# DigiDash.net
KiCad netlist of a schematic drawn in EAGLE
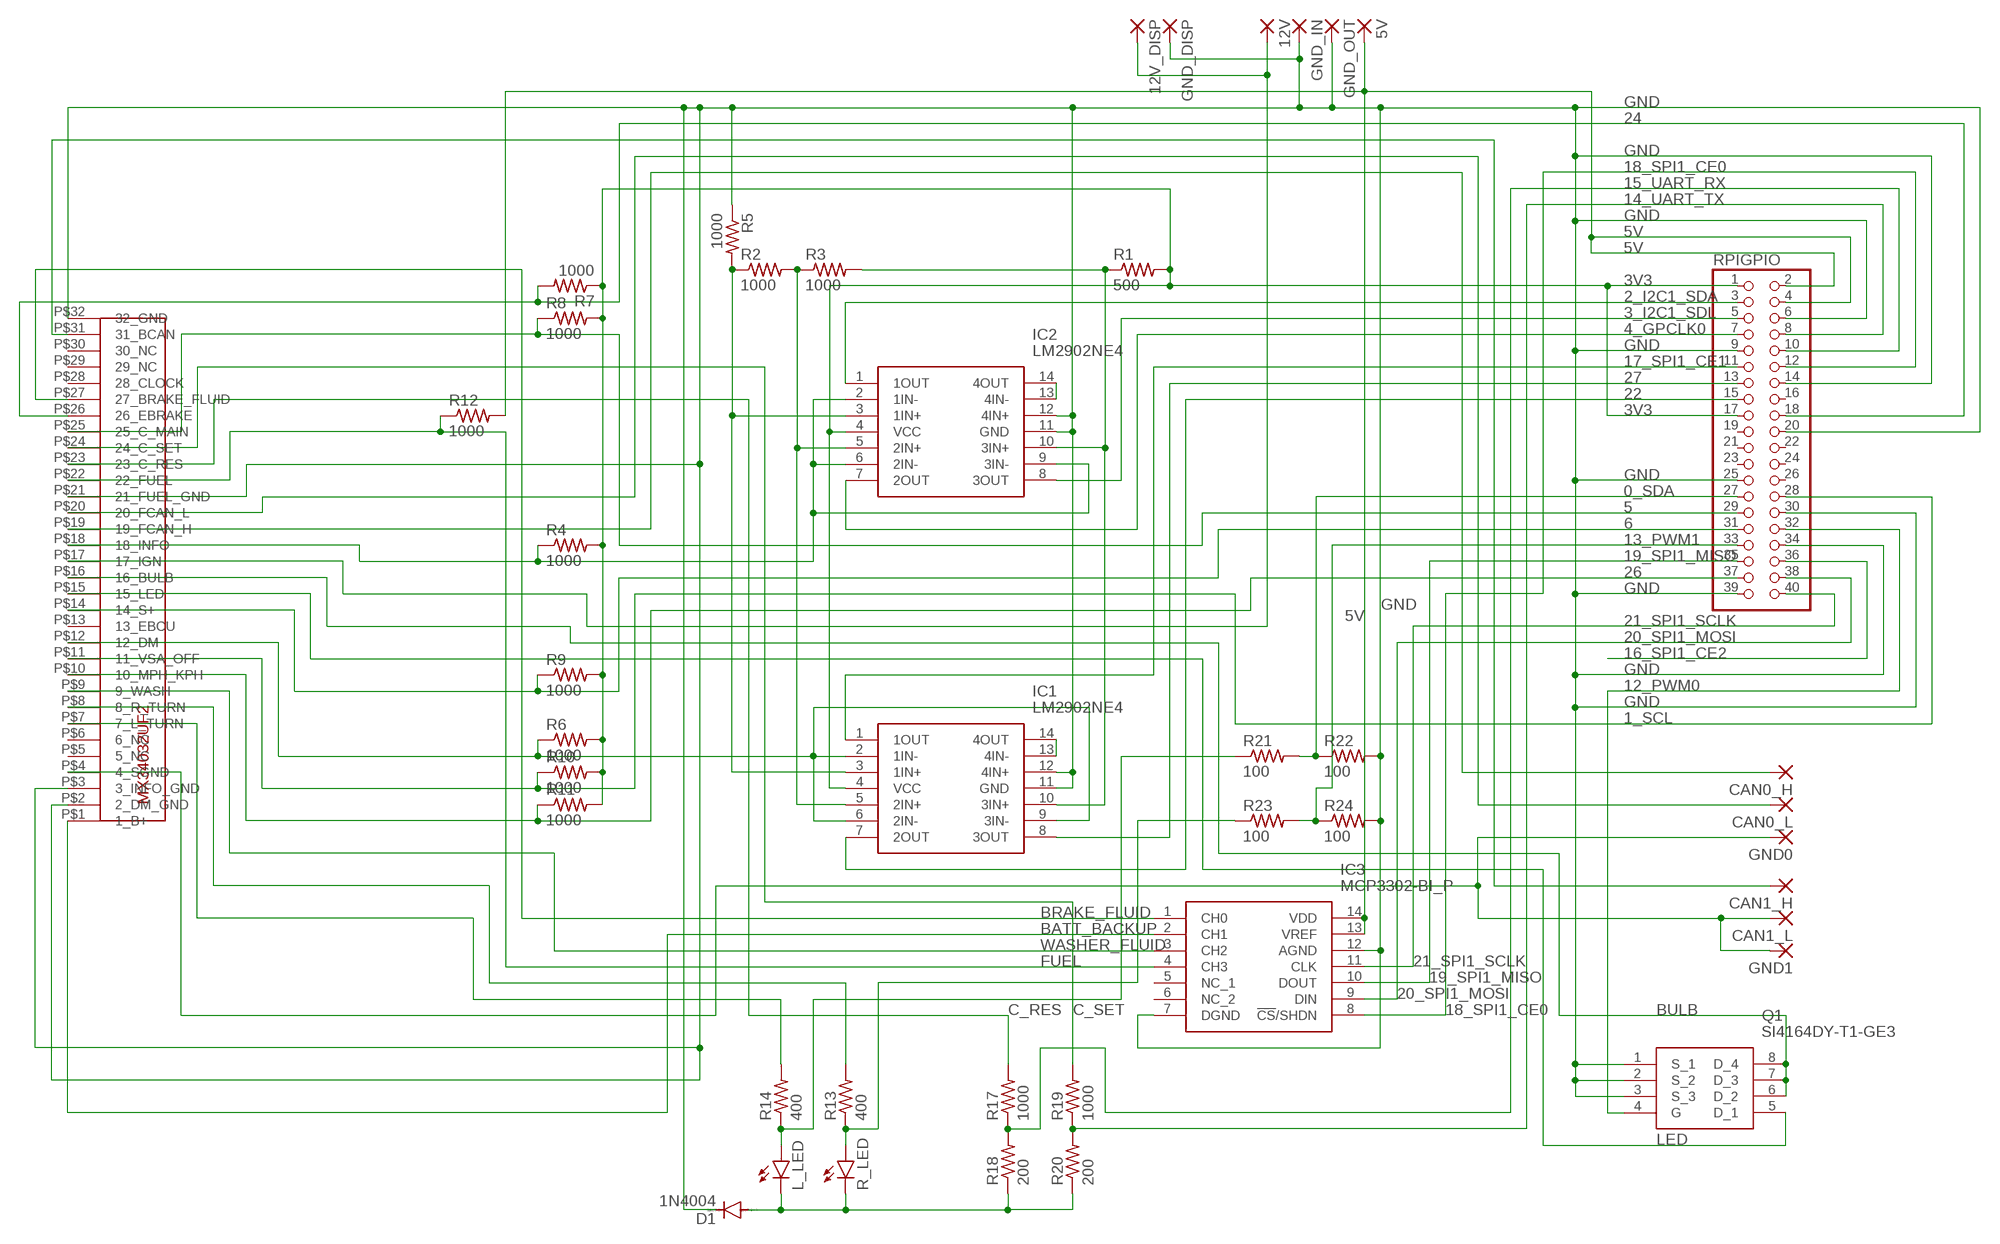
[diagram p0: schematic, sheet 1]

(export (version "E")
  (design (tool "Eeschema 10.0.6"))
  (components
    (comp (ref "5V")
      (value "3,81/1,4")
      (footprint "eagle-import:3,81_1,4")
      (libsource (lib "eagle-import") (part "3,81/1,4"))
    )
    (comp (ref "12V")
      (value "3,81/1,4")
      (footprint "eagle-import:3,81_1,4")
      (libsource (lib "eagle-import") (part "3,81/1,4"))
    )
    (comp (ref "12V_DISP")
      (value "3,81/1,4")
      (footprint "eagle-import:3,81_1,4")
      (libsource (lib "eagle-import") (part "3,81/1,4"))
    )
    (comp (ref "CAN0_H")
      (value "3,81/1,4")
      (footprint "eagle-import:3,81_1,4")
      (libsource (lib "eagle-import") (part "3,81/1,4"))
    )
    (comp (ref "CAN0_L")
      (value "3,81/1,4")
      (footprint "eagle-import:3,81_1,4")
      (libsource (lib "eagle-import") (part "3,81/1,4"))
    )
    (comp (ref "CAN1_H")
      (value "3,81/1,4")
      (footprint "eagle-import:3,81_1,4")
      (libsource (lib "eagle-import") (part "3,81/1,4"))
    )
    (comp (ref "CAN1_L")
      (value "3,81/1,4")
      (footprint "eagle-import:3,81_1,4")
      (libsource (lib "eagle-import") (part "3,81/1,4"))
    )
    (comp (ref "D1")
      (value "1N4004")
      (footprint "eagle-import:DO41-10")
      (libsource (lib "eagle-import") (part "1N4004"))
    )
    (comp (ref "GND0")
      (value "3,81/1,4")
      (footprint "eagle-import:3,81_1,4")
      (libsource (lib "eagle-import") (part "3,81/1,4"))
    )
    (comp (ref "GND1")
      (value "3,81/1,4")
      (footprint "eagle-import:3,81_1,4")
      (libsource (lib "eagle-import") (part "3,81/1,4"))
    )
    (comp (ref "GND_DISP")
      (value "3,81/1,4")
      (footprint "eagle-import:3,81_1,4")
      (libsource (lib "eagle-import") (part "3,81/1,4"))
    )
    (comp (ref "GND_IN")
      (value "3,81/1,4")
      (footprint "eagle-import:3,81_1,4")
      (libsource (lib "eagle-import") (part "3,81/1,4"))
    )
    (comp (ref "GND_OUT")
      (value "3,81/1,4")
      (footprint "eagle-import:3,81_1,4")
      (libsource (lib "eagle-import") (part "3,81/1,4"))
    )
    (comp (ref "IC1")
      (value "LM2902NE4")
      (footprint "eagle-import:DIP794W53P254L1930H508Q14N")
      (fields (field (name "MOUSER_PART_NUMBER") "595-LM2902NE4"))
      (libsource (lib "eagle-import") (part "LM2902NE4"))
    )
    (comp (ref "IC2")
      (value "LM2902NE4")
      (footprint "eagle-import:DIP794W53P254L1930H508Q14N")
      (fields (field (name "MOUSER_PART_NUMBER") "595-LM2902NE4"))
      (libsource (lib "eagle-import") (part "LM2902NE4"))
    )
    (comp (ref "IC3")
      (value "MCP3302-BI_P")
      (footprint "eagle-import:DIP781W56P254L1918H533Q14N")
      (fields
        (field (name "ARROW_PART_NUMBER") "MCP3302-BI/P")
        (field (name "MOUSER_PART_NUMBER") "579-MCP3302-BI/P")
      )
      (libsource (lib "eagle-import") (part "MCP3302-BI_P"))
    )
    (comp (ref "L_LED")
      (value "LED3MM")
      (footprint "eagle-import:LED3MM")
      (libsource (lib "eagle-import") (part "LED3MM"))
    )
    (comp (ref "Q1")
      (value "SI4164DY-T1-GE3")
      (footprint "eagle-import:SOIC127P600X175-8N")
      (fields (field (name "MOUSER_PART_NUMBER") "781-SI4164DY-T1-GE3"))
      (libsource (lib "eagle-import") (part "SI4164DY-T1-GE3"))
    )
    (comp (ref "R1")
      (value "500")
      (footprint "eagle-import:0204_7")
      (libsource (lib "eagle-import") (part "R-US_0204/7"))
    )
    (comp (ref "R2")
      (value "1000")
      (footprint "eagle-import:0204_7")
      (libsource (lib "eagle-import") (part "R-US_0204/7"))
    )
    (comp (ref "R3")
      (value "1000")
      (footprint "eagle-import:0204_7")
      (libsource (lib "eagle-import") (part "R-US_0204/7"))
    )
    (comp (ref "R4")
      (value "1000")
      (footprint "eagle-import:0204_7")
      (libsource (lib "eagle-import") (part "R-US_0204/7"))
    )
    (comp (ref "R5")
      (value "1000")
      (footprint "eagle-import:0204_7")
      (libsource (lib "eagle-import") (part "R-US_0204/7"))
    )
    (comp (ref "R6")
      (value "1000")
      (footprint "eagle-import:0204_7")
      (libsource (lib "eagle-import") (part "R-US_0204/7"))
    )
    (comp (ref "R7")
      (value "1000")
      (footprint "eagle-import:0204_7")
      (libsource (lib "eagle-import") (part "R-US_0204/7"))
    )
    (comp (ref "R8")
      (value "1000")
      (footprint "eagle-import:0204_7")
      (libsource (lib "eagle-import") (part "R-US_0204/7"))
    )
    (comp (ref "R9")
      (value "1000")
      (footprint "eagle-import:0204_7")
      (libsource (lib "eagle-import") (part "R-US_0204/7"))
    )
    (comp (ref "R10")
      (value "1000")
      (footprint "eagle-import:0204_7")
      (libsource (lib "eagle-import") (part "R-US_0204/7"))
    )
    (comp (ref "R11")
      (value "1000")
      (footprint "eagle-import:0204_7")
      (libsource (lib "eagle-import") (part "R-US_0204/7"))
    )
    (comp (ref "R12")
      (value "1000")
      (footprint "eagle-import:0204_7")
      (libsource (lib "eagle-import") (part "R-US_0204/7"))
    )
    (comp (ref "R13")
      (value "400")
      (footprint "eagle-import:0204_7")
      (libsource (lib "eagle-import") (part "R-US_0204/7"))
    )
    (comp (ref "R14")
      (value "400")
      (footprint "eagle-import:0204_7")
      (libsource (lib "eagle-import") (part "R-US_0204/7"))
    )
    (comp (ref "R17")
      (value "1000")
      (footprint "eagle-import:0204_7")
      (libsource (lib "eagle-import") (part "R-US_0204/7"))
    )
    (comp (ref "R18")
      (value "200")
      (footprint "eagle-import:0204_7")
      (libsource (lib "eagle-import") (part "R-US_0204/7"))
    )
    (comp (ref "R19")
      (value "1000")
      (footprint "eagle-import:0204_7")
      (libsource (lib "eagle-import") (part "R-US_0204/7"))
    )
    (comp (ref "R20")
      (value "200")
      (footprint "eagle-import:0204_7")
      (libsource (lib "eagle-import") (part "R-US_0204/7"))
    )
    (comp (ref "R21")
      (value "100")
      (footprint "eagle-import:0204_7")
      (libsource (lib "eagle-import") (part "R-US_0204/7"))
    )
    (comp (ref "R22")
      (value "100")
      (footprint "eagle-import:0204_7")
      (libsource (lib "eagle-import") (part "R-US_0204/7"))
    )
    (comp (ref "R23")
      (value "100")
      (footprint "eagle-import:0204_7")
      (libsource (lib "eagle-import") (part "R-US_0204/7"))
    )
    (comp (ref "R24")
      (value "100")
      (footprint "eagle-import:0204_7")
      (libsource (lib "eagle-import") (part "R-US_0204/7"))
    )
    (comp (ref "RPIGPIO")
      (value "PINHD-2X20")
      (footprint "eagle-import:2X20")
      (libsource (lib "eagle-import") (part "PINHD-2X20"))
    )
    (comp (ref "R_LED")
      (value "LED3MM")
      (footprint "eagle-import:LED3MM")
      (libsource (lib "eagle-import") (part "LED3MM"))
    )
    (comp (ref "U$1")
      (value "MX34032UF2")
      (footprint "eagle-import:MX34032UF2")
      (libsource (lib "eagle-import") (part "MX34032UF2"))
    )
  )
  (nets
    (net (code "1") (name "/0_SDA") (class "Default")
      (node (ref "R21") (pin "2") (pinfunction "2_2") (pintype "passive"))
      (node (ref "R22") (pin "1") (pinfunction "1_1") (pintype "passive"))
      (node (ref "RPIGPIO") (pin "27") (pinfunction "27_27") (pintype "passive"))
    )
    (net (code "2") (name "/1_SCL") (class "Default")
      (node (ref "R10") (pin "1") (pinfunction "1_1") (pintype "passive"))
      (node (ref "RPIGPIO") (pin "28") (pinfunction "28_28") (pintype "passive"))
      (node (ref "U$1") (pin "P$11") (pinfunction "11_VSA_OFF_P$11") (pintype "bidirectional"))
    )
    (net (code "3") (name "/2_I2C1_SDA") (class "Default")
      (node (ref "IC2") (pin "1") (pinfunction "1OUT_1") (pintype "bidirectional"))
      (node (ref "RPIGPIO") (pin "3") (pinfunction "3_3") (pintype "passive"))
    )
    (net (code "4") (name "/3V3") (class "Default")
      (node (ref "IC1") (pin "4") (pinfunction "VCC_4") (pintype "bidirectional"))
      (node (ref "IC2") (pin "4") (pinfunction "VCC_4") (pintype "bidirectional"))
      (node (ref "R1") (pin "2") (pinfunction "2_2") (pintype "passive"))
      (node (ref "R10") (pin "2") (pinfunction "2_2") (pintype "passive"))
      (node (ref "R11") (pin "2") (pinfunction "2_2") (pintype "passive"))
      (node (ref "R4") (pin "2") (pinfunction "2_2") (pintype "passive"))
      (node (ref "R6") (pin "2") (pinfunction "2_2") (pintype "passive"))
      (node (ref "R7") (pin "1") (pinfunction "1_1") (pintype "passive"))
      (node (ref "R8") (pin "2") (pinfunction "2_2") (pintype "passive"))
      (node (ref "R9") (pin "2") (pinfunction "2_2") (pintype "passive"))
      (node (ref "RPIGPIO") (pin "1") (pinfunction "1_1") (pintype "passive"))
      (node (ref "RPIGPIO") (pin "17") (pinfunction "17_17") (pintype "passive"))
    )
    (net (code "5") (name "/3_I2C1_SDL") (class "Default")
      (node (ref "IC2") (pin "8") (pinfunction "3OUT_8") (pintype "bidirectional"))
      (node (ref "RPIGPIO") (pin "5") (pinfunction "5_5") (pintype "passive"))
    )
    (net (code "6") (name "/4_GPCLK0") (class "Default")
      (node (ref "IC2") (pin "7") (pinfunction "2OUT_7") (pintype "bidirectional"))
      (node (ref "RPIGPIO") (pin "7") (pinfunction "7_7") (pintype "passive"))
    )
    (net (code "7") (name "/5") (class "Default")
      (node (ref "R8") (pin "1") (pinfunction "1_1") (pintype "passive"))
      (node (ref "RPIGPIO") (pin "29") (pinfunction "29_29") (pintype "passive"))
      (node (ref "U$1") (pin "P$25") (pinfunction "25_C_MAIN_P$25") (pintype "bidirectional"))
    )
    (net (code "8") (name "/5V") (class "Default")
      (node (ref "5V") (pin "1") (pinfunction "P_1") (pintype "passive"))
      (node (ref "IC3") (pin "13") (pinfunction "VREF_13") (pintype "bidirectional"))
      (node (ref "IC3") (pin "14") (pinfunction "VDD_14") (pintype "bidirectional"))
      (node (ref "R12") (pin "2") (pinfunction "2_2") (pintype "passive"))
      (node (ref "RPIGPIO") (pin "2") (pinfunction "2_2") (pintype "passive"))
      (node (ref "RPIGPIO") (pin "4") (pinfunction "4_4") (pintype "passive"))
    )
    (net (code "9") (name "/6") (class "Default")
      (node (ref "R9") (pin "1") (pinfunction "1_1") (pintype "passive"))
      (node (ref "RPIGPIO") (pin "31") (pinfunction "31_31") (pintype "passive"))
      (node (ref "U$1") (pin "P$14") (pinfunction "14_S+_P$14") (pintype "bidirectional"))
    )
    (net (code "10") (name "/12_PWM0") (class "Default")
      (node (ref "Q1") (pin "4") (pinfunction "G_4") (pintype "bidirectional"))
      (node (ref "RPIGPIO") (pin "32") (pinfunction "32_32") (pintype "passive"))
    )
    (net (code "11") (name "/13_PWM1") (class "Default")
      (node (ref "R23") (pin "2") (pinfunction "2_2") (pintype "passive"))
      (node (ref "R24") (pin "1") (pinfunction "1_1") (pintype "passive"))
      (node (ref "RPIGPIO") (pin "33") (pinfunction "33_33") (pintype "passive"))
    )
    (net (code "12") (name "/14_UART_TX") (class "Default")
      (node (ref "R19") (pin "1") (pinfunction "1_1") (pintype "passive"))
      (node (ref "R20") (pin "2") (pinfunction "2_2") (pintype "passive"))
      (node (ref "RPIGPIO") (pin "8") (pinfunction "8_8") (pintype "passive"))
    )
    (net (code "13") (name "/15_UART_RX") (class "Default")
      (node (ref "R17") (pin "1") (pinfunction "1_1") (pintype "passive"))
      (node (ref "R18") (pin "2") (pinfunction "2_2") (pintype "passive"))
      (node (ref "RPIGPIO") (pin "10") (pinfunction "10_10") (pintype "passive"))
    )
    (net (code "14") (name "/16_SPI1_CE2") (class "Default")
      (node (ref "RPIGPIO") (pin "36") (pinfunction "36_36") (pintype "passive"))
    )
    (net (code "15") (name "/17_SPI1_CE1") (class "Default")
      (node (ref "IC1") (pin "1") (pinfunction "1OUT_1") (pintype "bidirectional"))
      (node (ref "RPIGPIO") (pin "11") (pinfunction "11_11") (pintype "passive"))
    )
    (net (code "16") (name "/18_SPI1_CE0") (class "Default")
      (node (ref "IC3") (pin "8") (pinfunction "~{CS}/SHDN_8") (pintype "bidirectional"))
      (node (ref "RPIGPIO") (pin "12") (pinfunction "12_12") (pintype "passive"))
    )
    (net (code "17") (name "/19_SPI1_MISO") (class "Default")
      (node (ref "IC3") (pin "10") (pinfunction "DOUT_10") (pintype "bidirectional"))
      (node (ref "RPIGPIO") (pin "35") (pinfunction "35_35") (pintype "passive"))
    )
    (net (code "18") (name "/20_SPI1_MOSI") (class "Default")
      (node (ref "IC3") (pin "9") (pinfunction "DIN_9") (pintype "bidirectional"))
      (node (ref "RPIGPIO") (pin "38") (pinfunction "38_38") (pintype "passive"))
    )
    (net (code "19") (name "/21_SPI1_SCLK") (class "Default")
      (node (ref "IC3") (pin "11") (pinfunction "CLK_11") (pintype "bidirectional"))
      (node (ref "RPIGPIO") (pin "40") (pinfunction "40_40") (pintype "passive"))
    )
    (net (code "20") (name "/22") (class "Default")
      (node (ref "IC1") (pin "7") (pinfunction "2OUT_7") (pintype "bidirectional"))
      (node (ref "RPIGPIO") (pin "15") (pinfunction "15_15") (pintype "passive"))
    )
    (net (code "21") (name "/24") (class "Default")
      (node (ref "R7") (pin "2") (pinfunction "2_2") (pintype "passive"))
      (node (ref "RPIGPIO") (pin "18") (pinfunction "18_18") (pintype "passive"))
      (node (ref "U$1") (pin "P$26") (pinfunction "26_EBRAKE_P$26") (pintype "bidirectional"))
    )
    (net (code "22") (name "/26") (class "Default")
      (node (ref "R11") (pin "1") (pinfunction "1_1") (pintype "passive"))
      (node (ref "RPIGPIO") (pin "37") (pinfunction "37_37") (pintype "passive"))
      (node (ref "U$1") (pin "P$10") (pinfunction "10_MPH_KPH_P$10") (pintype "bidirectional"))
    )
    (net (code "23") (name "/27") (class "Default")
      (node (ref "IC1") (pin "8") (pinfunction "3OUT_8") (pintype "bidirectional"))
      (node (ref "RPIGPIO") (pin "13") (pinfunction "13_13") (pintype "passive"))
    )
    (net (code "24") (name "/BATT_BACKUP") (class "Default")
      (node (ref "IC3") (pin "2") (pinfunction "CH1_2") (pintype "bidirectional"))
      (node (ref "U$1") (pin "P$1") (pinfunction "1_B+_P$1") (pintype "bidirectional"))
    )
    (net (code "25") (name "/BRAKE_FLUID") (class "Default")
      (node (ref "IC3") (pin "1") (pinfunction "CH0_1") (pintype "bidirectional"))
      (node (ref "U$1") (pin "P$27") (pinfunction "27_BRAKE_FLUID_P$27") (pintype "bidirectional"))
    )
    (net (code "26") (name "/BULB") (class "Default")
      (node (ref "Q1") (pin "6") (pinfunction "D_2_6") (pintype "bidirectional"))
      (node (ref "Q1") (pin "7") (pinfunction "D_3_7") (pintype "bidirectional"))
      (node (ref "Q1") (pin "8") (pinfunction "D_4_8") (pintype "bidirectional"))
      (node (ref "U$1") (pin "P$16") (pinfunction "16_BULB_P$16") (pintype "bidirectional"))
    )
    (net (code "27") (name "/C_RES") (class "Default")
      (node (ref "R17") (pin "2") (pinfunction "2_2") (pintype "passive"))
      (node (ref "U$1") (pin "P$23") (pinfunction "23_C_RES_P$23") (pintype "bidirectional"))
    )
    (net (code "28") (name "/C_SET") (class "Default")
      (node (ref "R19") (pin "2") (pinfunction "2_2") (pintype "passive"))
      (node (ref "U$1") (pin "P$24") (pinfunction "24_C_SET_P$24") (pintype "bidirectional"))
    )
    (net (code "29") (name "/FUEL") (class "Default")
      (node (ref "IC3") (pin "4") (pinfunction "CH3_4") (pintype "bidirectional"))
      (node (ref "R12") (pin "1") (pinfunction "1_1") (pintype "passive"))
      (node (ref "U$1") (pin "P$22") (pinfunction "22_FUEL_P$22") (pintype "bidirectional"))
    )
    (net (code "30") (name "/GND") (class "Default")
      (node (ref "D1") (pin "C") (pinfunction "C_C") (pintype "passive"))
      (node (ref "GND_DISP") (pin "1") (pinfunction "P_1") (pintype "passive"))
      (node (ref "GND_IN") (pin "1") (pinfunction "P_1") (pintype "passive"))
      (node (ref "GND_OUT") (pin "1") (pinfunction "P_1") (pintype "passive"))
      (node (ref "IC1") (pin "11") (pinfunction "GND_11") (pintype "bidirectional"))
      (node (ref "IC1") (pin "12") (pinfunction "4IN+_12") (pintype "bidirectional"))
      (node (ref "IC2") (pin "11") (pinfunction "GND_11") (pintype "bidirectional"))
      (node (ref "IC2") (pin "12") (pinfunction "4IN+_12") (pintype "bidirectional"))
      (node (ref "IC3") (pin "12") (pinfunction "AGND_12") (pintype "bidirectional"))
      (node (ref "IC3") (pin "7") (pinfunction "DGND_7") (pintype "bidirectional"))
      (node (ref "Q1") (pin "1") (pinfunction "S_1_1") (pintype "bidirectional"))
      (node (ref "Q1") (pin "2") (pinfunction "S_2_2") (pintype "bidirectional"))
      (node (ref "Q1") (pin "3") (pinfunction "S_3_3") (pintype "bidirectional"))
      (node (ref "R22") (pin "2") (pinfunction "2_2") (pintype "passive"))
      (node (ref "R24") (pin "2") (pinfunction "2_2") (pintype "passive"))
      (node (ref "R5") (pin "1") (pinfunction "1_1") (pintype "passive"))
      (node (ref "RPIGPIO") (pin "14") (pinfunction "14_14") (pintype "passive"))
      (node (ref "RPIGPIO") (pin "20") (pinfunction "20_20") (pintype "passive"))
      (node (ref "RPIGPIO") (pin "25") (pinfunction "25_25") (pintype "passive"))
      (node (ref "RPIGPIO") (pin "30") (pinfunction "30_30") (pintype "passive"))
      (node (ref "RPIGPIO") (pin "34") (pinfunction "34_34") (pintype "passive"))
      (node (ref "RPIGPIO") (pin "39") (pinfunction "39_39") (pintype "passive"))
      (node (ref "RPIGPIO") (pin "6") (pinfunction "6_6") (pintype "passive"))
      (node (ref "RPIGPIO") (pin "9") (pinfunction "9_9") (pintype "passive"))
      (node (ref "U$1") (pin "P$2") (pinfunction "2_DM_GND_P$2") (pintype "bidirectional"))
      (node (ref "U$1") (pin "P$21") (pinfunction "21_FUEL_GND_P$21") (pintype "bidirectional"))
      (node (ref "U$1") (pin "P$3") (pinfunction "3_INFO_GND_P$3") (pintype "bidirectional"))
      (node (ref "U$1") (pin "P$32") (pinfunction "32_GND_P$32") (pintype "bidirectional"))
    )
    (net (code "31") (name "/LED") (class "Default")
      (node (ref "Q1") (pin "5") (pinfunction "D_1_5") (pintype "bidirectional"))
      (node (ref "U$1") (pin "P$15") (pinfunction "15_LED_P$15") (pintype "bidirectional"))
    )
    (net (code "32") (name "/WASHER_FLUID") (class "Default")
      (node (ref "IC3") (pin "3") (pinfunction "CH2_3") (pintype "bidirectional"))
      (node (ref "U$1") (pin "P$9") (pinfunction "9_WASH_P$9") (pintype "bidirectional"))
    )
    (net (code "33") (name "Net-(12V-P)") (class "Default")
      (node (ref "12V") (pin "1") (pinfunction "P_1") (pintype "passive"))
      (node (ref "12V_DISP") (pin "1") (pinfunction "P_1") (pintype "passive"))
      (node (ref "U$1") (pin "P$17") (pinfunction "17_IGN_P$17") (pintype "bidirectional"))
    )
    (net (code "34") (name "Net-(CAN0_H-P)") (class "Default")
      (node (ref "CAN0_H") (pin "1") (pinfunction "P_1") (pintype "passive"))
      (node (ref "U$1") (pin "P$19") (pinfunction "19_FCAN_H_P$19") (pintype "bidirectional"))
    )
    (net (code "35") (name "Net-(CAN0_L-P)") (class "Default")
      (node (ref "CAN0_L") (pin "1") (pinfunction "P_1") (pintype "passive"))
      (node (ref "U$1") (pin "P$20") (pinfunction "20_FCAN_L_P$20") (pintype "bidirectional"))
    )
    (net (code "36") (name "Net-(CAN1_H-P)") (class "Default")
      (node (ref "CAN1_H") (pin "1") (pinfunction "P_1") (pintype "passive"))
      (node (ref "U$1") (pin "P$31") (pinfunction "31_BCAN_P$31") (pintype "bidirectional"))
    )
    (net (code "37") (name "Net-(CAN1_L-P)") (class "Default")
      (node (ref "CAN1_L") (pin "1") (pinfunction "P_1") (pintype "passive"))
      (node (ref "GND0") (pin "1") (pinfunction "P_1") (pintype "passive"))
      (node (ref "GND1") (pin "1") (pinfunction "P_1") (pintype "passive"))
      (node (ref "U$1") (pin "P$4") (pinfunction "4_SGND_P$4") (pintype "bidirectional"))
    )
    (net (code "38") (name "Net-(IC1-1IN+)") (class "Default")
      (node (ref "IC1") (pin "3") (pinfunction "1IN+_3") (pintype "bidirectional"))
      (node (ref "IC2") (pin "3") (pinfunction "1IN+_3") (pintype "bidirectional"))
      (node (ref "R2") (pin "1") (pinfunction "1_1") (pintype "passive"))
      (node (ref "R5") (pin "2") (pinfunction "2_2") (pintype "passive"))
    )
    (net (code "39") (name "Net-(IC1-1IN-)") (class "Default")
      (node (ref "IC1") (pin "2") (pinfunction "1IN-_2") (pintype "bidirectional"))
      (node (ref "IC1") (pin "6") (pinfunction "2IN-_6") (pintype "bidirectional"))
      (node (ref "IC1") (pin "9") (pinfunction "3IN-_9") (pintype "bidirectional"))
      (node (ref "R6") (pin "1") (pinfunction "1_1") (pintype "passive"))
      (node (ref "U$1") (pin "P$12") (pinfunction "12_DM_P$12") (pintype "bidirectional"))
    )
    (net (code "40") (name "Net-(IC1-2IN+)") (class "Default")
      (node (ref "IC1") (pin "5") (pinfunction "2IN+_5") (pintype "bidirectional"))
      (node (ref "IC2") (pin "5") (pinfunction "2IN+_5") (pintype "bidirectional"))
      (node (ref "R2") (pin "2") (pinfunction "2_2") (pintype "passive"))
      (node (ref "R3") (pin "1") (pinfunction "1_1") (pintype "passive"))
    )
    (net (code "41") (name "Net-(IC1-3IN+)") (class "Default")
      (node (ref "IC1") (pin "10") (pinfunction "3IN+_10") (pintype "bidirectional"))
      (node (ref "IC2") (pin "10") (pinfunction "3IN+_10") (pintype "bidirectional"))
      (node (ref "R1") (pin "1") (pinfunction "1_1") (pintype "passive"))
      (node (ref "R3") (pin "2") (pinfunction "2_2") (pintype "passive"))
    )
    (net (code "42") (name "Net-(IC1-4IN-)") (class "Default")
      (node (ref "IC1") (pin "13") (pinfunction "4IN-_13") (pintype "bidirectional"))
      (node (ref "IC1") (pin "14") (pinfunction "4OUT_14") (pintype "bidirectional"))
    )
    (net (code "43") (name "Net-(IC2-1IN-)") (class "Default")
      (node (ref "IC2") (pin "2") (pinfunction "1IN-_2") (pintype "bidirectional"))
      (node (ref "IC2") (pin "6") (pinfunction "2IN-_6") (pintype "bidirectional"))
      (node (ref "IC2") (pin "9") (pinfunction "3IN-_9") (pintype "bidirectional"))
      (node (ref "R4") (pin "1") (pinfunction "1_1") (pintype "passive"))
      (node (ref "U$1") (pin "P$18") (pinfunction "18_INFO_P$18") (pintype "bidirectional"))
    )
    (net (code "44") (name "Net-(IC2-4IN-)") (class "Default")
      (node (ref "IC2") (pin "13") (pinfunction "4IN-_13") (pintype "bidirectional"))
      (node (ref "IC2") (pin "14") (pinfunction "4OUT_14") (pintype "bidirectional"))
    )
    (net (code "45") (name "Net-(L_LED-C)") (class "Default")
      (node (ref "D1") (pin "A") (pinfunction "A_A") (pintype "passive"))
      (node (ref "L_LED") (pin "K") (pinfunction "C_K") (pintype "passive"))
      (node (ref "R18") (pin "1") (pinfunction "1_1") (pintype "passive"))
      (node (ref "R20") (pin "1") (pinfunction "1_1") (pintype "passive"))
      (node (ref "R_LED") (pin "K") (pinfunction "C_K") (pintype "passive"))
    )
    (net (code "46") (name "Net-(L_LED-PadA)") (class "Default")
      (node (ref "L_LED") (pin "A") (pinfunction "A_A") (pintype "passive"))
      (node (ref "R14") (pin "1") (pinfunction "1_1") (pintype "passive"))
      (node (ref "R21") (pin "1") (pinfunction "1_1") (pintype "passive"))
    )
    (net (code "47") (name "Net-(R13-Pad1)") (class "Default")
      (node (ref "R13") (pin "1") (pinfunction "1_1") (pintype "passive"))
      (node (ref "R23") (pin "1") (pinfunction "1_1") (pintype "passive"))
      (node (ref "R_LED") (pin "A") (pinfunction "A_A") (pintype "passive"))
    )
    (net (code "48") (name "Net-(U$1-7_L_TURN)") (class "Default")
      (node (ref "R14") (pin "2") (pinfunction "2_2") (pintype "passive"))
      (node (ref "U$1") (pin "P$7") (pinfunction "7_L_TURN_P$7") (pintype "bidirectional"))
    )
    (net (code "49") (name "Net-(U$1-8_R_TURN)") (class "Default")
      (node (ref "R13") (pin "2") (pinfunction "2_2") (pintype "passive"))
      (node (ref "U$1") (pin "P$8") (pinfunction "8_R_TURN_P$8") (pintype "bidirectional"))
    )
    (net (code "50") (name "unconnected-(IC3-NC_1-Pad5)") (class "Default")
      (node (ref "IC3") (pin "5") (pinfunction "NC_1_5") (pintype "bidirectional"))
    )
    (net (code "51") (name "unconnected-(IC3-NC_2-Pad6)") (class "Default")
      (node (ref "IC3") (pin "6") (pinfunction "NC_2_6") (pintype "bidirectional"))
    )
    (net (code "52") (name "unconnected-(RPIGPIO-Pad16)") (class "Default")
      (node (ref "RPIGPIO") (pin "16") (pinfunction "16_16") (pintype "passive"))
    )
    (net (code "53") (name "unconnected-(RPIGPIO-Pad19)") (class "Default")
      (node (ref "RPIGPIO") (pin "19") (pinfunction "19_19") (pintype "passive"))
    )
    (net (code "54") (name "unconnected-(RPIGPIO-Pad21)") (class "Default")
      (node (ref "RPIGPIO") (pin "21") (pinfunction "21_21") (pintype "passive"))
    )
    (net (code "55") (name "unconnected-(RPIGPIO-Pad22)") (class "Default")
      (node (ref "RPIGPIO") (pin "22") (pinfunction "22_22") (pintype "passive"))
    )
    (net (code "56") (name "unconnected-(RPIGPIO-Pad23)") (class "Default")
      (node (ref "RPIGPIO") (pin "23") (pinfunction "23_23") (pintype "passive"))
    )
    (net (code "57") (name "unconnected-(RPIGPIO-Pad24)") (class "Default")
      (node (ref "RPIGPIO") (pin "24") (pinfunction "24_24") (pintype "passive"))
    )
    (net (code "58") (name "unconnected-(RPIGPIO-Pad26)") (class "Default")
      (node (ref "RPIGPIO") (pin "26") (pinfunction "26_26") (pintype "passive"))
    )
    (net (code "59") (name "unconnected-(U$1-5_NC-PadP$5)") (class "Default")
      (node (ref "U$1") (pin "P$5") (pinfunction "5_NC_P$5") (pintype "bidirectional"))
    )
    (net (code "60") (name "unconnected-(U$1-6_NC-PadP$6)") (class "Default")
      (node (ref "U$1") (pin "P$6") (pinfunction "6_NC_P$6") (pintype "bidirectional"))
    )
    (net (code "61") (name "unconnected-(U$1-13_EBCU-PadP$13)") (class "Default")
      (node (ref "U$1") (pin "P$13") (pinfunction "13_EBCU_P$13") (pintype "bidirectional"))
    )
    (net (code "62") (name "unconnected-(U$1-28_CLOCK-PadP$28)") (class "Default")
      (node (ref "U$1") (pin "P$28") (pinfunction "28_CLOCK_P$28") (pintype "bidirectional"))
    )
    (net (code "63") (name "unconnected-(U$1-29_NC-PadP$29)") (class "Default")
      (node (ref "U$1") (pin "P$29") (pinfunction "29_NC_P$29") (pintype "bidirectional"))
    )
    (net (code "64") (name "unconnected-(U$1-30_NC-PadP$30)") (class "Default")
      (node (ref "U$1") (pin "P$30") (pinfunction "30_NC_P$30") (pintype "bidirectional"))
    )
  )
)
